# ESP32_Processor.net
KiCad netlist of a schematic drawn in Altium Designer
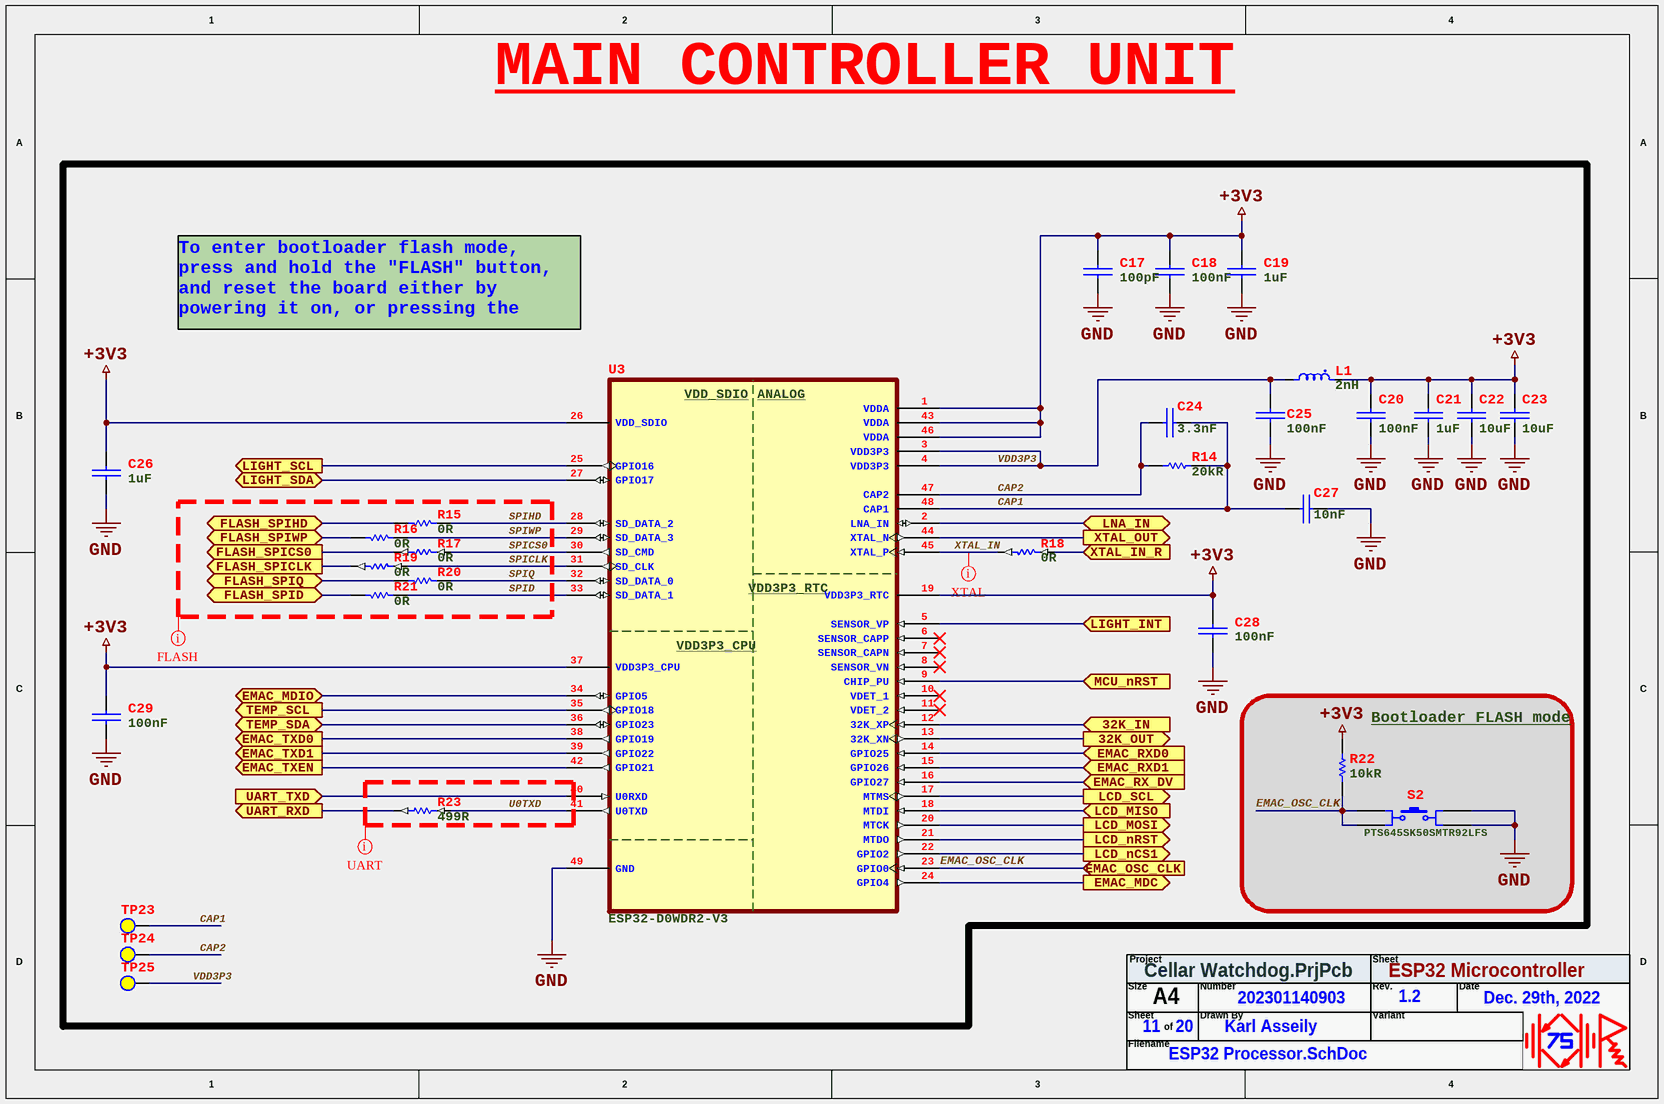
[diagram p0: ESP32 Processor.SchDoc]

(export (version "E")
  (design (tool "Eeschema 10.0.6"))
  (components
    (comp (ref "C17")
      (value "100pF")
      (footprint "CAP_0603")
      (description "100 pF ±10% 50V Ceramic Capacitor X7R 0603 (1608 Metric)")
      (fields
        (field (name "MANUFACTURER") "Yageo")
        (field (name "MANUFACTURER PART NUMBER") "CC0603KRX7R9BB101")
      )
      (libsource (lib "Cellar Watchdog") (part "CAP_100pF-50V-10%_0603"))
    )
    (comp (ref "C18")
      (value "100nF")
      (footprint "CAP_0603")
      (description "0.1 µF ±10% 50V Ceramic Capacitor X7R 0603 (1608 Metric)")
      (fields
        (field (name "MANUFACTURER") "Yageo")
        (field (name "MANUFACTURER PART NUMBER") "CC0603KRX7R9BB104")
      )
      (libsource (lib "Cellar Watchdog") (part "CAP_0.1uF-50V-10%_0603"))
    )
    (comp (ref "C19")
      (value "1uF")
      (footprint "CAP_0805")
      (description "1 µF ±10% 16V Ceramic Capacitor X7R 0603 (1608 Metric)")
      (fields
        (field (name "MANUFACTURER") "Yageo")
        (field (name "MANUFACTURER PART NUMBER") "CC0603KRX7R7BB105")
      )
      (libsource (lib "Cellar Watchdog") (part "CAP_1uF-16V-10%_0603"))
    )
    (comp (ref "C20")
      (value "100nF")
      (footprint "CAP_0603")
      (description "0.1 µF ±10% 50V Ceramic Capacitor X7R 0603 (1608 Metric)")
      (fields
        (field (name "MANUFACTURER") "Yageo")
        (field (name "MANUFACTURER PART NUMBER") "CC0603KRX7R9BB104")
      )
      (libsource (lib "Cellar Watchdog") (part "CAP_0.1uF-50V-10%_0603"))
    )
    (comp (ref "C21")
      (value "1uF")
      (footprint "CAP_0805")
      (description "1 µF ±10% 16V Ceramic Capacitor X7R 0603 (1608 Metric)")
      (fields
        (field (name "MANUFACTURER") "Yageo")
        (field (name "MANUFACTURER PART NUMBER") "CC0603KRX7R7BB105")
      )
      (libsource (lib "Cellar Watchdog") (part "CAP_1uF-16V-10%_0603"))
    )
    (comp (ref "C22")
      (value "10uF")
      (footprint "CAP_1206")
      (description "10 µF ±10% 25V Ceramic Capacitor X7R 1206 (3216 Metric)")
      (fields
        (field (name "MANUFACTURER") "Yageo")
        (field (name "MANUFACTURER PART NUMBER") "CC1206KKX7R8BB106")
      )
      (libsource (lib "Cellar Watchdog") (part "CAP_10uF-25V-10%_1206"))
    )
    (comp (ref "C23")
      (value "10uF")
      (footprint "CAP_1206")
      (description "10 µF ±10% 25V Ceramic Capacitor X7R 1206 (3216 Metric)")
      (fields
        (field (name "MANUFACTURER") "Yageo")
        (field (name "MANUFACTURER PART NUMBER") "CC1206KKX7R8BB106")
      )
      (libsource (lib "Cellar Watchdog") (part "CAP_10uF-25V-10%_1206"))
    )
    (comp (ref "C24")
      (value "3.3nF")
      (footprint "CAP_0603")
      (description "3300 pF ±10% 50V Ceramic Capacitor X7R 0603 (1608 Metric)")
      (fields
        (field (name "MANUFACTURER") "Yageo")
        (field (name "MANUFACTURER PART NUMBER") "CC0603KRX7R9BB332")
      )
      (libsource (lib "Cellar Watchdog") (part "CAP_3.3nF-50V-10%_0603"))
    )
    (comp (ref "C25")
      (value "100nF")
      (footprint "CAP_0603")
      (description "0.1 µF ±10% 50V Ceramic Capacitor X7R 0603 (1608 Metric)")
      (fields
        (field (name "MANUFACTURER") "Yageo")
        (field (name "MANUFACTURER PART NUMBER") "CC0603KRX7R9BB104")
      )
      (libsource (lib "Cellar Watchdog") (part "CAP_0.1uF-50V-10%_0603"))
    )
    (comp (ref "C26")
      (value "1uF")
      (footprint "CAP_0805")
      (description "1 µF ±10% 16V Ceramic Capacitor X7R 0603 (1608 Metric)")
      (fields
        (field (name "MANUFACTURER") "Yageo")
        (field (name "MANUFACTURER PART NUMBER") "CC0603KRX7R7BB105")
      )
      (libsource (lib "Cellar Watchdog") (part "CAP_1uF-16V-10%_0603"))
    )
    (comp (ref "C27")
      (value "10nF")
      (footprint "CAP_0603")
      (description "10000 pF ±10% 50V Ceramic Capacitor X7R 0603 (1608 Metric)")
      (fields
        (field (name "MANUFACTURER") "Yageo")
        (field (name "MANUFACTURER PART NUMBER") "CC0603KRX7R9BB103")
      )
      (libsource (lib "Cellar Watchdog") (part "CAP_10nF-50V-10%_0603"))
    )
    (comp (ref "C28")
      (value "100nF")
      (footprint "CAP_0603")
      (description "0.1 µF ±10% 50V Ceramic Capacitor X7R 0603 (1608 Metric)")
      (fields
        (field (name "MANUFACTURER") "Yageo")
        (field (name "MANUFACTURER PART NUMBER") "CC0603KRX7R9BB104")
      )
      (libsource (lib "Cellar Watchdog") (part "CAP_0.1uF-50V-10%_0603"))
    )
    (comp (ref "C29")
      (value "100nF")
      (footprint "CAP_0603")
      (description "0.1 µF ±10% 50V Ceramic Capacitor X7R 0603 (1608 Metric)")
      (fields
        (field (name "MANUFACTURER") "Yageo")
        (field (name "MANUFACTURER PART NUMBER") "CC0603KRX7R9BB104")
      )
      (libsource (lib "Cellar Watchdog") (part "CAP_0.1uF-50V-10%_0603"))
    )
    (comp (ref "L1")
      (value "2nH")
      (footprint "IND_0402")
      (description "2 nH Unshielded Multilayer Inductor 900 mA 90mOhm Max 0402 (1005 Metric)")
      (fields
        (field (name "MANUFACTURER") "Murata")
        (field (name "MANUFACTURER PART NUMBER") "LQG15HN2N0C02D")
      )
      (libsource (lib "Cellar Watchdog") (part "IND_2nH-900mA-10%_0402"))
    )
    (comp (ref "R14")
      (value "20kR")
      (footprint "RES_0603")
      (description "20 kOhms ±1% 0.1W, 1/10W Chip Resistor 0603 (1608 Metric) Moisture Resistant Thick Film")
      (fields
        (field (name "MANUFACTURER") "Yageo")
        (field (name "MANUFACTURER PART NUMBER") "RC0603FR-0720KL")
      )
      (libsource (lib "Cellar Watchdog") (part "RES_20kR-100mW-1%_0603"))
    )
    (comp (ref "R15")
      (value "0R")
      (footprint "RES_0603")
      (description "0 Ohms Jumper Chip Resistor 0603 (1608 Metric) Moisture Resistant Thick Film")
      (fields
        (field (name "MANUFACTURER") "Yageo")
        (field (name "MANUFACTURER PART NUMBER") "RC0603FR-070RL")
      )
      (libsource (lib "Cellar Watchdog") (part "RES_0R-100mW-1%_0603"))
    )
    (comp (ref "R16")
      (value "0R")
      (footprint "RES_0603")
      (description "0 Ohms Jumper Chip Resistor 0603 (1608 Metric) Moisture Resistant Thick Film")
      (fields
        (field (name "MANUFACTURER") "Yageo")
        (field (name "MANUFACTURER PART NUMBER") "RC0603FR-070RL")
      )
      (libsource (lib "Cellar Watchdog") (part "RES_0R-100mW-1%_0603"))
    )
    (comp (ref "R17")
      (value "0R")
      (footprint "RES_0603")
      (description "0 Ohms Jumper Chip Resistor 0603 (1608 Metric) Moisture Resistant Thick Film")
      (fields
        (field (name "MANUFACTURER") "Yageo")
        (field (name "MANUFACTURER PART NUMBER") "RC0603FR-070RL")
      )
      (libsource (lib "Cellar Watchdog") (part "RES_0R-100mW-1%_0603"))
    )
    (comp (ref "R18")
      (value "0R")
      (footprint "RES_0603")
      (description "0 Ohms Jumper Chip Resistor 0603 (1608 Metric) Moisture Resistant Thick Film")
      (fields
        (field (name "MANUFACTURER") "Yageo")
        (field (name "MANUFACTURER PART NUMBER") "RC0603FR-070RL")
      )
      (libsource (lib "Cellar Watchdog") (part "RES_0R-100mW-1%_0603"))
    )
    (comp (ref "R19")
      (value "0R")
      (footprint "RES_0603")
      (description "0 Ohms Jumper Chip Resistor 0603 (1608 Metric) Moisture Resistant Thick Film")
      (fields
        (field (name "MANUFACTURER") "Yageo")
        (field (name "MANUFACTURER PART NUMBER") "RC0603FR-070RL")
      )
      (libsource (lib "Cellar Watchdog") (part "RES_0R-100mW-1%_0603"))
    )
    (comp (ref "R20")
      (value "0R")
      (footprint "RES_0603")
      (description "0 Ohms Jumper Chip Resistor 0603 (1608 Metric) Moisture Resistant Thick Film")
      (fields
        (field (name "MANUFACTURER") "Yageo")
        (field (name "MANUFACTURER PART NUMBER") "RC0603FR-070RL")
      )
      (libsource (lib "Cellar Watchdog") (part "RES_0R-100mW-1%_0603"))
    )
    (comp (ref "R21")
      (value "0R")
      (footprint "RES_0603")
      (description "0 Ohms Jumper Chip Resistor 0603 (1608 Metric) Moisture Resistant Thick Film")
      (fields
        (field (name "MANUFACTURER") "Yageo")
        (field (name "MANUFACTURER PART NUMBER") "RC0603FR-070RL")
      )
      (libsource (lib "Cellar Watchdog") (part "RES_0R-100mW-1%_0603"))
    )
    (comp (ref "R22")
      (value "10kR")
      (footprint "RES_0603")
      (description "10 kOhms ±1% 0.1W, 1/10W Chip Resistor 0603 (1608 Metric) Moisture Resistant Thick Film")
      (fields
        (field (name "MANUFACTURER") "Yageo")
        (field (name "MANUFACTURER PART NUMBER") "RC0603FR-0710KL")
      )
      (libsource (lib "Cellar Watchdog") (part "RES_10kR-100mW-1%_0603"))
    )
    (comp (ref "R23")
      (value "499R")
      (footprint "RES_0603")
      (description "499 Ohms ±1% 0.1W, 1/10W Chip Resistor 0603 (1608 Metric) Moisture Resistant Thick Film")
      (fields
        (field (name "MANUFACTURER") "Yageo")
        (field (name "MANUFACTURER PART NUMBER") "RC0603FR-07499RL")
      )
      (libsource (lib "Cellar Watchdog") (part "RES_499R-100mW-1%_0603"))
    )
    (comp (ref "S2")
      (value "PTS645SK50SMTR92LFS")
      (footprint "SW_TACTILE-SPST_PTS645SK50SMTR92LFS_SMD")
      (description "Tactile Switch SPST-NO Top Actuated Surface Mount")
      (fields (field (name "MANUFACTURER") "ITT C&K"))
      (libsource (lib "Cellar Watchdog") (part "SW4-NO-SPST_PTS645SK50SMTR92LFS_SMD"))
    )
    (comp (ref "TP23")
      (value "CAP1")
      (footprint "TEST POINT PAD")
      (description "PCB Test Point")
      (libsource (lib "Cellar Watchdog") (part "Test Point"))
    )
    (comp (ref "TP24")
      (value "CAP2")
      (footprint "TEST POINT PAD")
      (description "PCB Test Point")
      (libsource (lib "Cellar Watchdog") (part "Test Point"))
    )
    (comp (ref "TP25")
      (value "VDD3P3")
      (footprint "TEST POINT PAD")
      (description "PCB Test Point")
      (libsource (lib "Cellar Watchdog") (part "Test Point"))
    )
    (comp (ref "U3")
      (value "ESP32-D0WDR2-V3")
      (footprint "IC_QFN35P500X500X90-49N")
      (fields (field (name "MANUFACTURER") "Espressif Systems"))
      (libsource (lib "Cellar Watchdog") (part "IC_ESP32-D0WDR2-V3"))
    )
  )
  (nets
    (net (code "1") (name "+3V3") (class "Default")
      (node (ref "C17") (pin "1") (pinfunction "1_1") (pintype "passive"))
      (node (ref "C18") (pin "1") (pinfunction "1_1") (pintype "passive"))
      (node (ref "C19") (pin "1") (pinfunction "1_1") (pintype "passive"))
      (node (ref "C20") (pin "1") (pinfunction "1_1") (pintype "passive"))
      (node (ref "C21") (pin "1") (pinfunction "1_1") (pintype "passive"))
      (node (ref "C22") (pin "1") (pinfunction "1_1") (pintype "passive"))
      (node (ref "C23") (pin "1") (pinfunction "1_1") (pintype "passive"))
      (node (ref "C26") (pin "1") (pinfunction "1_1") (pintype "passive"))
      (node (ref "C28") (pin "1") (pinfunction "1_1") (pintype "passive"))
      (node (ref "C29") (pin "1") (pinfunction "1_1") (pintype "passive"))
      (node (ref "L1") (pin "1") (pinfunction "1_1") (pintype "passive"))
      (node (ref "R22") (pin "2") (pinfunction "2_2") (pintype "passive"))
      (node (ref "U3") (pin "1") (pinfunction "VDDA_1") (pintype "power_in"))
      (node (ref "U3") (pin "19") (pinfunction "VDD3P3_RTC_19") (pintype "power_in"))
      (node (ref "U3") (pin "26") (pinfunction "VDD_SDIO_26") (pintype "power_in"))
      (node (ref "U3") (pin "37") (pinfunction "VDD3P3_CPU_37") (pintype "power_in"))
      (node (ref "U3") (pin "43") (pinfunction "VDDA_43") (pintype "power_in"))
      (node (ref "U3") (pin "46") (pinfunction "VDDA_46") (pintype "power_in"))
    )
    (net (code "2") (name "/32K_IN") (class "Default")
      (node (ref "U3") (pin "12") (pinfunction "32K_XP_12") (pintype "input"))
    )
    (net (code "3") (name "/32K_OUT") (class "Default")
      (node (ref "U3") (pin "13") (pinfunction "32K_XN_13") (pintype "output"))
    )
    (net (code "4") (name "/CAP1") (class "Default")
      (node (ref "C24") (pin "2") (pinfunction "2_2") (pintype "passive"))
      (node (ref "C27") (pin "1") (pinfunction "1_1") (pintype "passive"))
      (node (ref "R14") (pin "2") (pinfunction "2_2") (pintype "passive"))
      (node (ref "TP23") (pin "TP") (pinfunction "TP_TP") (pintype "passive"))
      (node (ref "U3") (pin "48") (pinfunction "CAP1_48") (pintype "passive"))
    )
    (net (code "5") (name "/CAP2") (class "Default")
      (node (ref "C24") (pin "1") (pinfunction "1_1") (pintype "passive"))
      (node (ref "R14") (pin "1") (pinfunction "1_1") (pintype "passive"))
      (node (ref "TP24") (pin "TP") (pinfunction "TP_TP") (pintype "passive"))
      (node (ref "U3") (pin "47") (pinfunction "CAP2_47") (pintype "passive"))
    )
    (net (code "6") (name "/EMAC_MDC") (class "Default")
      (node (ref "U3") (pin "24") (pinfunction "GPIO4_24") (pintype "output"))
    )
    (net (code "7") (name "/EMAC_MDIO") (class "Default")
      (node (ref "U3") (pin "34") (pinfunction "GPIO5_34") (pintype "bidirectional"))
    )
    (net (code "8") (name "/EMAC_OSC_CLK") (class "Default")
      (node (ref "R22") (pin "1") (pinfunction "1_1") (pintype "passive"))
      (node (ref "S2") (pin "1") (pinfunction "1_1") (pintype "passive"))
      (node (ref "S2") (pin "2") (pinfunction "2_2") (pintype "passive"))
      (node (ref "U3") (pin "23") (pinfunction "GPIO0_23") (pintype "input"))
    )
    (net (code "9") (name "/EMAC_RXD0") (class "Default")
      (node (ref "U3") (pin "14") (pinfunction "GPIO25_14") (pintype "input"))
    )
    (net (code "10") (name "/EMAC_RXD1") (class "Default")
      (node (ref "U3") (pin "15") (pinfunction "GPIO26_15") (pintype "input"))
    )
    (net (code "11") (name "/EMAC_RX_DV") (class "Default")
      (node (ref "U3") (pin "16") (pinfunction "GPIO27_16") (pintype "input"))
    )
    (net (code "12") (name "/EMAC_TXD0") (class "Default")
      (node (ref "U3") (pin "38") (pinfunction "GPIO19_38") (pintype "output"))
    )
    (net (code "13") (name "/EMAC_TXD1") (class "Default")
      (node (ref "U3") (pin "39") (pinfunction "GPIO22_39") (pintype "output"))
    )
    (net (code "14") (name "/EMAC_TXEN") (class "Default")
      (node (ref "U3") (pin "42") (pinfunction "GPIO21_42") (pintype "output"))
    )
    (net (code "15") (name "/FLASH_SPICLK") (class "Default")
      (node (ref "R19") (pin "1") (pinfunction "1_1") (pintype "passive"))
    )
    (net (code "16") (name "/FLASH_SPICS0") (class "Default")
      (node (ref "R17") (pin "1") (pinfunction "1_1") (pintype "passive"))
    )
    (net (code "17") (name "/FLASH_SPID") (class "Default")
      (node (ref "R21") (pin "1") (pinfunction "1_1") (pintype "passive"))
    )
    (net (code "18") (name "/FLASH_SPIHD") (class "Default")
      (node (ref "R15") (pin "1") (pinfunction "1_1") (pintype "passive"))
    )
    (net (code "19") (name "/FLASH_SPIQ") (class "Default")
      (node (ref "R20") (pin "1") (pinfunction "1_1") (pintype "passive"))
    )
    (net (code "20") (name "/FLASH_SPIWP") (class "Default")
      (node (ref "R16") (pin "1") (pinfunction "1_1") (pintype "passive"))
    )
    (net (code "21") (name "/LCD_MISO") (class "Default")
      (node (ref "U3") (pin "18") (pinfunction "MTDI_18") (pintype "input"))
    )
    (net (code "22") (name "/LCD_MOSI") (class "Default")
      (node (ref "U3") (pin "20") (pinfunction "MTCK_20") (pintype "output"))
    )
    (net (code "23") (name "/LCD_SCL") (class "Default")
      (node (ref "U3") (pin "17") (pinfunction "MTMS_17") (pintype "output"))
    )
    (net (code "24") (name "/LCD_nCS1") (class "Default")
      (node (ref "U3") (pin "22") (pinfunction "GPIO2_22") (pintype "output"))
    )
    (net (code "25") (name "/LCD_nRST") (class "Default")
      (node (ref "U3") (pin "21") (pinfunction "MTDO_21") (pintype "output"))
    )
    (net (code "26") (name "/LIGHT_INT") (class "Default")
      (node (ref "U3") (pin "5") (pinfunction "SENSOR_VP_5") (pintype "input"))
    )
    (net (code "27") (name "/LIGHT_SCL") (class "Default")
      (node (ref "U3") (pin "25") (pinfunction "GPIO16_25") (pintype "output"))
    )
    (net (code "28") (name "/LIGHT_SDA") (class "Default")
      (node (ref "U3") (pin "27") (pinfunction "GPIO17_27") (pintype "bidirectional"))
    )
    (net (code "29") (name "/LNA_IN") (class "Default")
      (node (ref "U3") (pin "2") (pinfunction "LNA_IN_2") (pintype "bidirectional"))
    )
    (net (code "30") (name "/MCU_nRST") (class "Default")
      (node (ref "U3") (pin "9") (pinfunction "CHIP_PU_9") (pintype "input"))
    )
    (net (code "31") (name "/SPICLK") (class "Default")
      (node (ref "R19") (pin "2") (pinfunction "2_2") (pintype "passive"))
      (node (ref "U3") (pin "31") (pinfunction "SD_CLK_31") (pintype "output"))
    )
    (net (code "32") (name "/SPICS0") (class "Default")
      (node (ref "R17") (pin "2") (pinfunction "2_2") (pintype "passive"))
      (node (ref "U3") (pin "30") (pinfunction "SD_CMD_30") (pintype "output"))
    )
    (net (code "33") (name "/SPID") (class "Default")
      (node (ref "R21") (pin "2") (pinfunction "2_2") (pintype "passive"))
      (node (ref "U3") (pin "33") (pinfunction "SD_DATA_1_33") (pintype "bidirectional"))
    )
    (net (code "34") (name "/SPIHD") (class "Default")
      (node (ref "R15") (pin "2") (pinfunction "2_2") (pintype "passive"))
      (node (ref "U3") (pin "28") (pinfunction "SD_DATA_2_28") (pintype "bidirectional"))
    )
    (net (code "35") (name "/SPIQ") (class "Default")
      (node (ref "R20") (pin "2") (pinfunction "2_2") (pintype "passive"))
      (node (ref "U3") (pin "32") (pinfunction "SD_DATA_0_32") (pintype "bidirectional"))
    )
    (net (code "36") (name "/SPIWP") (class "Default")
      (node (ref "R16") (pin "2") (pinfunction "2_2") (pintype "passive"))
      (node (ref "U3") (pin "29") (pinfunction "SD_DATA_3_29") (pintype "bidirectional"))
    )
    (net (code "37") (name "/TEMP_SCL") (class "Default")
      (node (ref "U3") (pin "35") (pinfunction "GPIO18_35") (pintype "output"))
    )
    (net (code "38") (name "/TEMP_SDA") (class "Default")
      (node (ref "U3") (pin "36") (pinfunction "GPIO23_36") (pintype "bidirectional"))
    )
    (net (code "39") (name "/U0TXD") (class "Default")
      (node (ref "R23") (pin "2") (pinfunction "2_2") (pintype "input"))
      (node (ref "U3") (pin "41") (pinfunction "U0TXD_41") (pintype "output"))
    )
    (net (code "40") (name "/UART_RXD") (class "Default")
      (node (ref "R23") (pin "1") (pinfunction "1_1") (pintype "output"))
    )
    (net (code "41") (name "/UART_TXD") (class "Default")
      (node (ref "U3") (pin "40") (pinfunction "U0RXD_40") (pintype "input"))
    )
    (net (code "42") (name "/VDD3P3") (class "Default")
      (node (ref "C25") (pin "1") (pinfunction "1_1") (pintype "passive"))
      (node (ref "L1") (pin "2") (pinfunction "2_2") (pintype "passive"))
      (node (ref "TP25") (pin "TP") (pinfunction "TP_TP") (pintype "passive"))
      (node (ref "U3") (pin "3") (pinfunction "VDD3P3_3") (pintype "power_in"))
      (node (ref "U3") (pin "4") (pinfunction "VDD3P3_4") (pintype "power_in"))
    )
    (net (code "43") (name "/XTAL_IN") (class "Default")
      (node (ref "R18") (pin "1") (pinfunction "1_1") (pintype "passive"))
      (node (ref "U3") (pin "45") (pinfunction "XTAL_P_45") (pintype "input"))
    )
    (net (code "44") (name "/XTAL_IN_R") (class "Default")
      (node (ref "R18") (pin "2") (pinfunction "2_2") (pintype "passive"))
    )
    (net (code "45") (name "/XTAL_OUT") (class "Default")
      (node (ref "U3") (pin "44") (pinfunction "XTAL_N_44") (pintype "output"))
    )
    (net (code "46") (name "GND") (class "Default")
      (node (ref "C17") (pin "2") (pinfunction "2_2") (pintype "passive"))
      (node (ref "C18") (pin "2") (pinfunction "2_2") (pintype "passive"))
      (node (ref "C19") (pin "2") (pinfunction "2_2") (pintype "passive"))
      (node (ref "C20") (pin "2") (pinfunction "2_2") (pintype "passive"))
      (node (ref "C21") (pin "2") (pinfunction "2_2") (pintype "passive"))
      (node (ref "C22") (pin "2") (pinfunction "2_2") (pintype "passive"))
      (node (ref "C23") (pin "2") (pinfunction "2_2") (pintype "passive"))
      (node (ref "C25") (pin "2") (pinfunction "2_2") (pintype "passive"))
      (node (ref "C26") (pin "2") (pinfunction "2_2") (pintype "passive"))
      (node (ref "C27") (pin "2") (pinfunction "2_2") (pintype "passive"))
      (node (ref "C28") (pin "2") (pinfunction "2_2") (pintype "passive"))
      (node (ref "C29") (pin "2") (pinfunction "2_2") (pintype "passive"))
      (node (ref "S2") (pin "3") (pinfunction "3_3") (pintype "power_in"))
      (node (ref "S2") (pin "4") (pinfunction "4_4") (pintype "power_in"))
      (node (ref "U3") (pin "49") (pinfunction "GND_49") (pintype "power_in"))
    )
    (net (code "47") (name "unconnected-(U3-SENSOR_CAPN-Pad7)") (class "Default")
      (node (ref "U3") (pin "7") (pinfunction "SENSOR_CAPN_7") (pintype "input+no_connect"))
    )
    (net (code "48") (name "unconnected-(U3-SENSOR_CAPP-Pad6)") (class "Default")
      (node (ref "U3") (pin "6") (pinfunction "SENSOR_CAPP_6") (pintype "input+no_connect"))
    )
    (net (code "49") (name "unconnected-(U3-SENSOR_VN-Pad8)") (class "Default")
      (node (ref "U3") (pin "8") (pinfunction "SENSOR_VN_8") (pintype "input+no_connect"))
    )
    (net (code "50") (name "unconnected-(U3-VDET_1-Pad10)") (class "Default")
      (node (ref "U3") (pin "10") (pinfunction "VDET_1_10") (pintype "input+no_connect"))
    )
    (net (code "51") (name "unconnected-(U3-VDET_2-Pad11)") (class "Default")
      (node (ref "U3") (pin "11") (pinfunction "VDET_2_11") (pintype "input+no_connect"))
    )
  )
)
